# I2C_Jog_Controller.net
KiCad netlist of a schematic drawn in Altium Designer
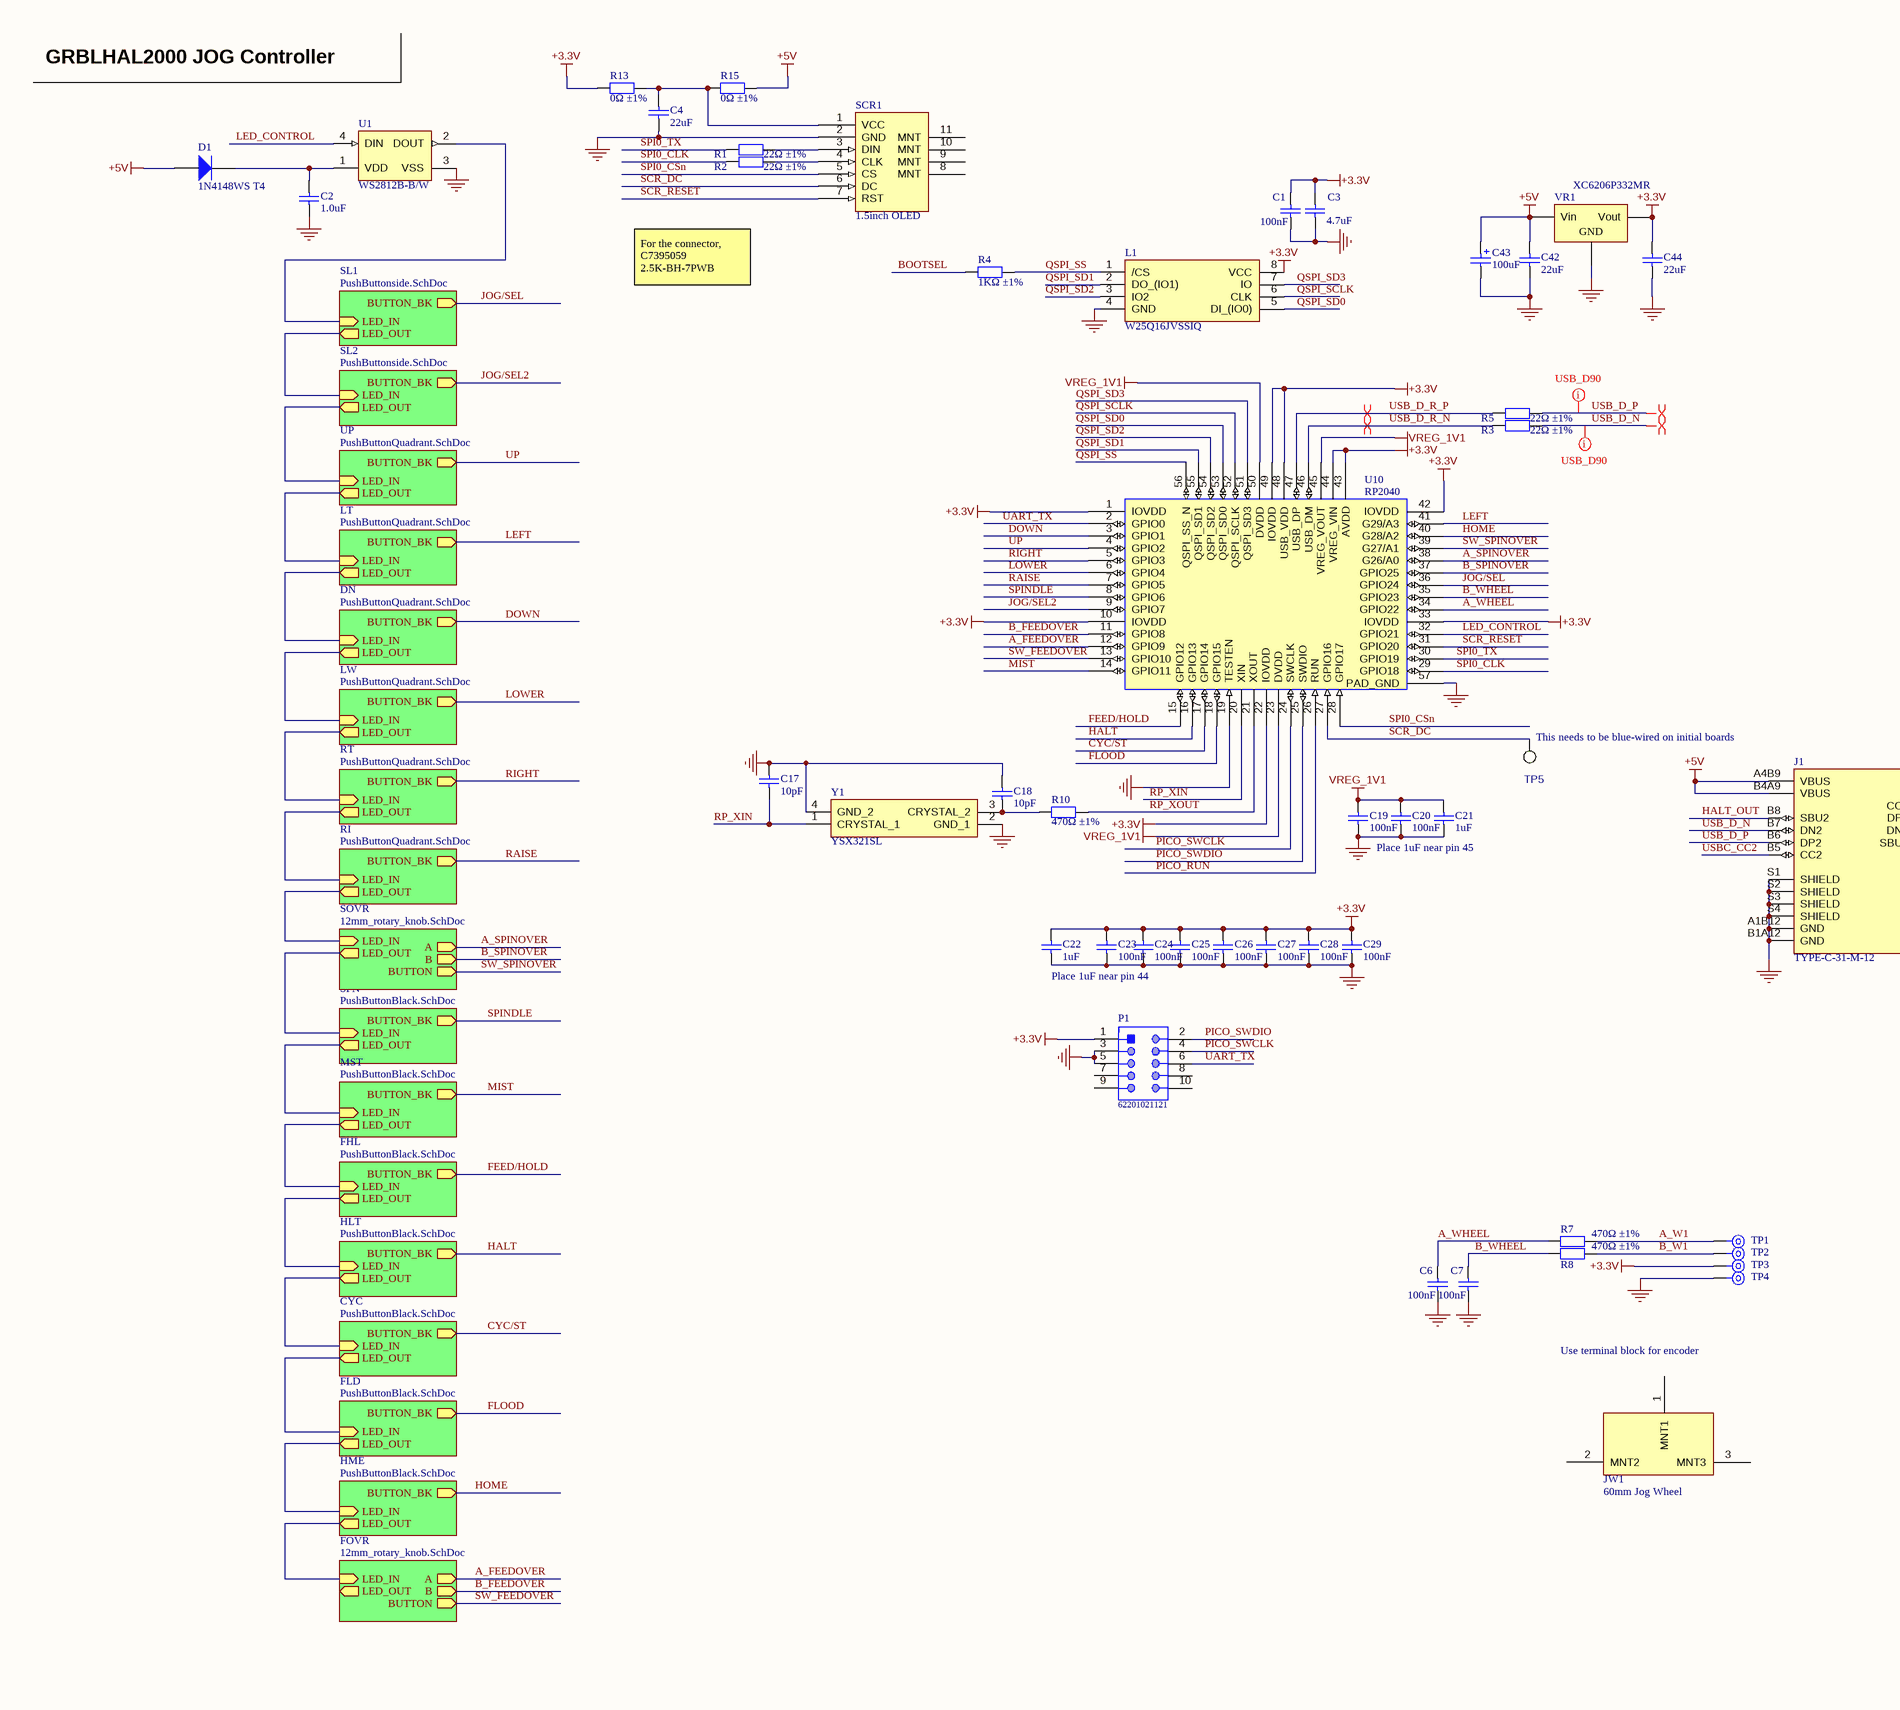
[diagram p0: I2C_Jog_Controller.SchDoc, left]
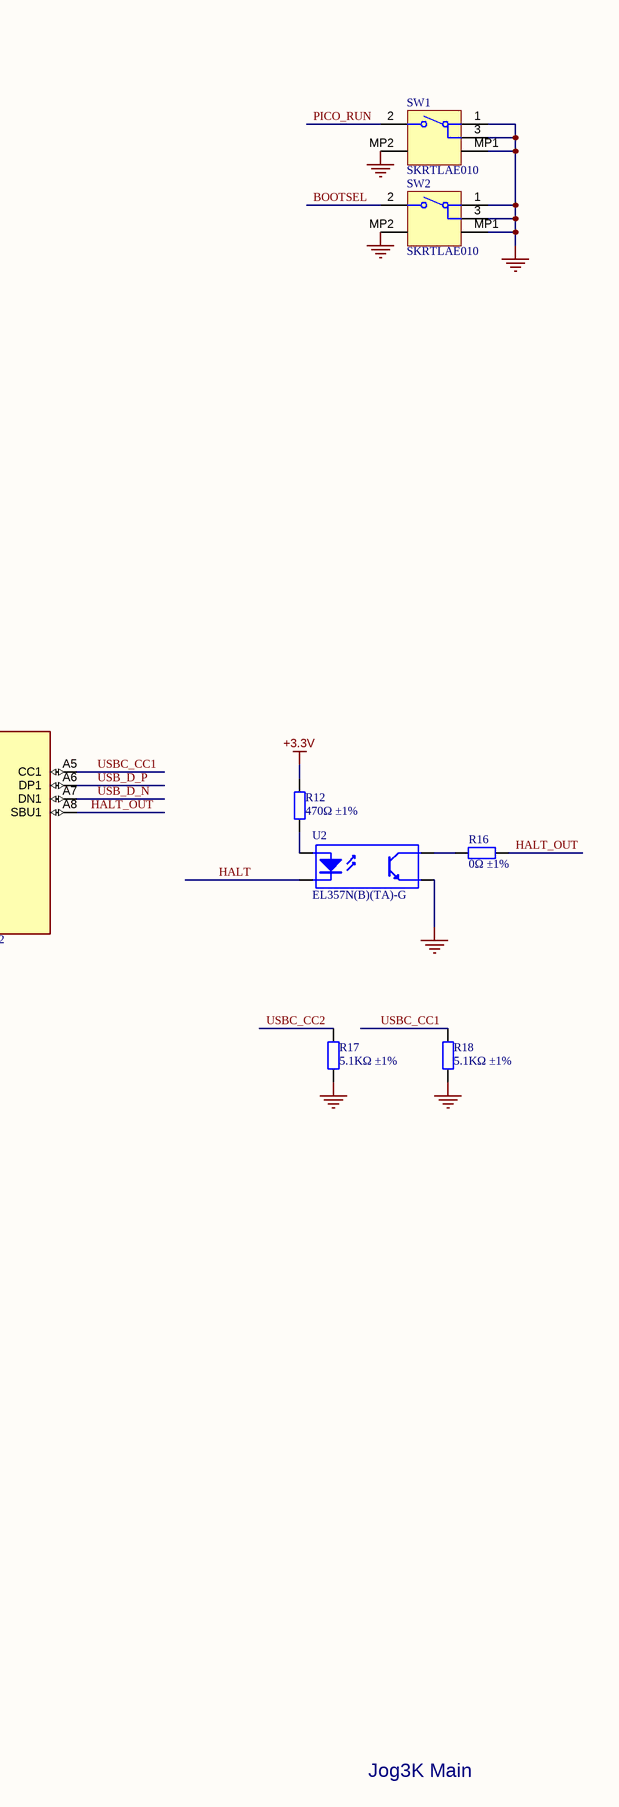
[diagram p1: I2C_Jog_Controller.SchDoc, right]

(export (version "E")
  (design (tool "Eeschema 10.0.6"))
  (components
    (comp (ref "C1")
      (value "100nF")
      (footprint "0603_C")
      (description "Chip capacitors")
      (fields (field (name "MANUFACTURER") "YAGEO") (field (name "PARTNUMBER") "CC0603KRX7R9BB104"))
      (libsource (lib "Cap") (part "0603 100nF (104) 10% 50V"))
    )
    (comp (ref "C2")
      (value "1.0uF")
      (footprint "0402_C")
      (description "Chip capacitor")
      (fields
        (field (name "MANUFACTURER") "Samsung Electro-Mechanics")
        (field (name "PARTNUMBER") "CL05A105KA5NQNC")
      )
      (libsource (lib "Cap") (part "0402 1.0uF (105) 10% 25V"))
    )
    (comp (ref "C3")
      (value "4.7uF")
      (footprint "0603_C")
      (description "Chip capacitors")
      (fields
        (field (name "MANUFACTURER") "Samsung Electro-Mechanics")
        (field (name "PARTNUMBER") "CL10A475KO8NNNC")
      )
      (libsource (lib "Cap") (part "0603 4.7uF (475) 10% 16V"))
    )
    (comp (ref "C4")
      (value "22uF")
      (footprint "0805_C")
      (description "Chip capacitors")
      (fields
        (field (name "MANUFACTURER") "Samsung Electro-Mechanics")
        (field (name "PARTNUMBER") "CL21A226MAQNNNE")
      )
      (libsource (lib "Cap") (part "0805 22uF (226) 20% 25V"))
    )
    (comp (ref "C6")
      (value "100nF")
      (footprint "0603_C")
      (description "Chip capacitors")
      (fields (field (name "MANUFACTURER") "YAGEO") (field (name "PARTNUMBER") "CC0603KRX7R9BB104"))
      (libsource (lib "Cap") (part "0603 100nF (104) 10% 50V"))
    )
    (comp (ref "C7")
      (value "100nF")
      (footprint "0603_C")
      (description "Chip capacitors")
      (fields (field (name "MANUFACTURER") "YAGEO") (field (name "PARTNUMBER") "CC0603KRX7R9BB104"))
      (libsource (lib "Cap") (part "0603 100nF (104) 10% 50V"))
    )
    (comp (ref "C17")
      (value "10pF")
      (footprint "0603_C")
      (description "Chip capacitors")
      (fields
        (field (name "MANUFACTURER") "Samsung Electro-Mechanics")
        (field (name "PARTNUMBER") "CL10C100JB8NNNC")
      )
      (libsource (lib "Cap") (part "0603 10pF (100) 5% 50V"))
    )
    (comp (ref "C18")
      (value "10pF")
      (footprint "0603_C")
      (description "Chip capacitors")
      (fields
        (field (name "MANUFACTURER") "Samsung Electro-Mechanics")
        (field (name "PARTNUMBER") "CL10C100JB8NNNC")
      )
      (libsource (lib "Cap") (part "0603 10pF (100) 5% 50V"))
    )
    (comp (ref "C19")
      (value "100nF")
      (footprint "0603_C")
      (description "Chip capacitors")
      (fields (field (name "MANUFACTURER") "YAGEO") (field (name "PARTNUMBER") "CC0603KRX7R9BB104"))
      (libsource (lib "Cap") (part "0603 100nF (104) 10% 50V"))
    )
    (comp (ref "C20")
      (value "100nF")
      (footprint "0603_C")
      (description "Chip capacitors")
      (fields (field (name "MANUFACTURER") "YAGEO") (field (name "PARTNUMBER") "CC0603KRX7R9BB104"))
      (libsource (lib "Cap") (part "0603 100nF (104) 10% 50V"))
    )
    (comp (ref "C21")
      (value "1uF")
      (footprint "0603_C")
      (description "Chip capacitors")
      (fields
        (field (name "MANUFACTURER") "Samsung Electro-Mechanics")
        (field (name "PARTNUMBER") "CL10A105KB8NNNC")
      )
      (libsource (lib "Cap") (part "0603 1uF (105) 10% 50V"))
    )
    (comp (ref "C22")
      (value "1uF")
      (footprint "0603_C")
      (description "Chip capacitors")
      (fields
        (field (name "MANUFACTURER") "Samsung Electro-Mechanics")
        (field (name "PARTNUMBER") "CL10A105KB8NNNC")
      )
      (libsource (lib "Cap") (part "0603 1uF (105) 10% 50V"))
    )
    (comp (ref "C23")
      (value "100nF")
      (footprint "0603_C")
      (description "Chip capacitors")
      (fields (field (name "MANUFACTURER") "YAGEO") (field (name "PARTNUMBER") "CC0603KRX7R9BB104"))
      (libsource (lib "Cap") (part "0603 100nF (104) 10% 50V"))
    )
    (comp (ref "C24")
      (value "100nF")
      (footprint "0603_C")
      (description "Chip capacitors")
      (fields (field (name "MANUFACTURER") "YAGEO") (field (name "PARTNUMBER") "CC0603KRX7R9BB104"))
      (libsource (lib "Cap") (part "0603 100nF (104) 10% 50V"))
    )
    (comp (ref "C25")
      (value "100nF")
      (footprint "0603_C")
      (description "Chip capacitors")
      (fields (field (name "MANUFACTURER") "YAGEO") (field (name "PARTNUMBER") "CC0603KRX7R9BB104"))
      (libsource (lib "Cap") (part "0603 100nF (104) 10% 50V"))
    )
    (comp (ref "C26")
      (value "100nF")
      (footprint "0603_C")
      (description "Chip capacitors")
      (fields (field (name "MANUFACTURER") "YAGEO") (field (name "PARTNUMBER") "CC0603KRX7R9BB104"))
      (libsource (lib "Cap") (part "0603 100nF (104) 10% 50V"))
    )
    (comp (ref "C27")
      (value "100nF")
      (footprint "0603_C")
      (description "Chip capacitors")
      (fields (field (name "MANUFACTURER") "YAGEO") (field (name "PARTNUMBER") "CC0603KRX7R9BB104"))
      (libsource (lib "Cap") (part "0603 100nF (104) 10% 50V"))
    )
    (comp (ref "C28")
      (value "100nF")
      (footprint "0603_C")
      (description "Chip capacitors")
      (fields (field (name "MANUFACTURER") "YAGEO") (field (name "PARTNUMBER") "CC0603KRX7R9BB104"))
      (libsource (lib "Cap") (part "0603 100nF (104) 10% 50V"))
    )
    (comp (ref "C29")
      (value "100nF")
      (footprint "0603_C")
      (description "Chip capacitors")
      (fields (field (name "MANUFACTURER") "YAGEO") (field (name "PARTNUMBER") "CC0603KRX7R9BB104"))
      (libsource (lib "Cap") (part "0603 100nF (104) 10% 50V"))
    )
    (comp (ref "C42")
      (value "22uF")
      (footprint "0805_C")
      (description "Chip capacitors")
      (fields
        (field (name "MANUFACTURER") "Samsung Electro-Mechanics")
        (field (name "PARTNUMBER") "CL21A226MAQNNNE")
      )
      (libsource (lib "Cap") (part "0805 22uF (226) 20% 25V"))
    )
    (comp (ref "C43")
      (value "100uF")
      (footprint "CASE-B_3528")
      (description "Tantalum capacitor")
      (fields (field (name "MANUFACTURER") "AVX") (field (name "PARTNUMBER") "TAJB107K006RNJ"))
      (libsource (lib "Cap") (part "3528 100uF (107) 10% 6.3V"))
    )
    (comp (ref "C44")
      (value "22uF")
      (footprint "0805_C")
      (description "Chip capacitors")
      (fields
        (field (name "MANUFACTURER") "Samsung Electro-Mechanics")
        (field (name "PARTNUMBER") "CL21A226MAQNNNE")
      )
      (libsource (lib "Cap") (part "0805 22uF (226) 20% 25V"))
    )
    (comp (ref "D1")
      (value "1N4148WS T4")
      (footprint "SOD-323")
      (description "二极管")
      (libsource (lib "Diode") (part "SOD-323 1N4148WS T4"))
    )
    (comp (ref "J1")
      (value "TYPE-C-31-M-12")
      (footprint "HRO_TYPE-C-31-M-12")
      (description "USB Connectors 24 Receptacle 1 8.94*7.3mm RoHS")
      (fields (field (name "MF") "HRO Electronics Co., Ltd."))
      (libsource (lib "Universal_CNC_Breakout") (part "TYPE-C-31-M-12"))
    )
    (comp (ref "JW1")
      (value "60mm Jog Wheel")
      (footprint "60mm_Jog_wheel")
      (libsource (lib "I2C_Jog_Controller") (part "60mm_Jog_Wheel"))
    )
    (comp (ref "L1")
      (value "W25Q16JVSSIQ")
      (footprint "SamacSys:SOIC127P780X195-8N")
      (description "SPI NOR FLASH 16Mbit")
      (libsource (lib "*") (part "W25Q128JVSIQ_TR"))
    )
    (comp (ref "P1")
      (value "62201021121")
      (footprint "62201021121")
      (description "THT Vertical Pin Header WR-PHD, Pitch 1.27 mm, Dual Row, 10 pins")
      (fields (field (name "MANUFACTURER") "Wurth Elektronik") (field (name "PUBLISHER") "WurthElektronik"))
      (libsource (lib "Altium Content Vault") (part "WE-CN-2P-M-R10"))
    )
    (comp (ref "R1")
      (value "22Ω ±1%")
      (footprint "0603_R")
      (description "Chip resistor")
      (fields (field (name "MANUFACTURER") "Uniroyal Elec") (field (name "PARTNUMBER") "0603WAF220JT5E"))
      (libsource (lib "RES") (part "0603 22R (22R0) 1%"))
    )
    (comp (ref "R2")
      (value "22Ω ±1%")
      (footprint "0603_R")
      (description "Chip resistor")
      (fields (field (name "MANUFACTURER") "Uniroyal Elec") (field (name "PARTNUMBER") "0603WAF220JT5E"))
      (libsource (lib "RES") (part "0603 22R (22R0) 1%"))
    )
    (comp (ref "R3")
      (value "22Ω ±1%")
      (footprint "0603_R")
      (description "Chip resistor")
      (fields (field (name "MANUFACTURER") "Uniroyal Elec") (field (name "PARTNUMBER") "0603WAF220JT5E"))
      (libsource (lib "RES") (part "0603 22R (22R0) 1%"))
    )
    (comp (ref "R4")
      (value "1KΩ ±1%")
      (footprint "0603_R")
      (description "Chip resistor")
      (fields (field (name "MANUFACTURER") "Uniroyal Elec") (field (name "PARTNUMBER") "0603WAF1001T5E"))
      (libsource (lib "RES") (part "0603 1K (1001) 1%"))
    )
    (comp (ref "R5")
      (value "22Ω ±1%")
      (footprint "0603_R")
      (description "Chip resistor")
      (fields (field (name "MANUFACTURER") "Uniroyal Elec") (field (name "PARTNUMBER") "0603WAF220JT5E"))
      (libsource (lib "RES") (part "0603 22R (22R0) 1%"))
    )
    (comp (ref "R7")
      (value "470Ω ±1%")
      (footprint "0603_R")
      (description "Chip resistor")
      (fields (field (name "MANUFACTURER") "Uniroyal Elec") (field (name "PARTNUMBER") "0603WAF4700T5E"))
      (libsource (lib "RES") (part "0603 470R (4700) 1%"))
    )
    (comp (ref "R8")
      (value "470Ω ±1%")
      (footprint "0603_R")
      (description "Chip resistor")
      (fields (field (name "MANUFACTURER") "Uniroyal Elec") (field (name "PARTNUMBER") "0603WAF4700T5E"))
      (libsource (lib "RES") (part "0603 470R (4700) 1%"))
    )
    (comp (ref "R10")
      (value "470Ω ±1%")
      (footprint "0603_R")
      (description "Chip resistor")
      (fields (field (name "MANUFACTURER") "Uniroyal Elec") (field (name "PARTNUMBER") "0603WAF4700T5E"))
      (libsource (lib "RES") (part "0603 470R (4700) 1%"))
    )
    (comp (ref "R12")
      (value "470Ω ±1%")
      (footprint "0603_R")
      (description "Chip resistor")
      (fields (field (name "MANUFACTURER") "Uniroyal Elec") (field (name "PARTNUMBER") "0603WAF4700T5E"))
      (libsource (lib "") (part "0603 470R (4700) 1%_1"))
    )
    (comp (ref "R13")
      (value "0Ω ±1%")
      (footprint "0603_R")
      (description "Chip resistor")
      (fields (field (name "MANUFACTURER") "Uniroyal Elec") (field (name "PARTNUMBER") "0603WAF0000T5E"))
      (libsource (lib "RES") (part "0603 0R (0R0) 1%"))
    )
    (comp (ref "R15")
      (value "0Ω ±1%")
      (footprint "0603_R")
      (description "Chip resistor")
      (fields (field (name "MANUFACTURER") "Uniroyal Elec") (field (name "PARTNUMBER") "0603WAF0000T5E"))
      (libsource (lib "RES") (part "0603 0R (0R0) 1%"))
    )
    (comp (ref "R16")
      (value "0Ω ±1%")
      (footprint "0603_R")
      (description "Chip resistor")
      (fields (field (name "MANUFACTURER") "Uniroyal Elec") (field (name "PARTNUMBER") "0603WAF0000T5E"))
      (libsource (lib "RES") (part "0603 0R (0R0) 1%"))
    )
    (comp (ref "R17")
      (value "5.1KΩ ±1%")
      (footprint "0603_R")
      (description "Chip resistor")
      (fields (field (name "MANUFACTURER") "Uniroyal Elec") (field (name "PARTNUMBER") "0603WAF5101T5E"))
      (libsource (lib "RES") (part "0603 5.1K (5101) 1%"))
    )
    (comp (ref "R18")
      (value "5.1KΩ ±1%")
      (footprint "0603_R")
      (description "Chip resistor")
      (fields (field (name "MANUFACTURER") "Uniroyal Elec") (field (name "PARTNUMBER") "0603WAF5101T5E"))
      (libsource (lib "RES") (part "0603 5.1K (5101) 1%"))
    )
    (comp (ref "SCR1")
      (value "1.5inch OLED")
      (footprint "1.5inch_Waveshare_OLED")
      (libsource (lib "I2C_Jog_Controller") (part "1.5inch Waveshare OLED screen"))
    )
    (comp (ref "SW1")
      (value "SKRTLAE010")
      (footprint "ALPS-SKRTLAE010_V")
      (description "Side Push Type, 250 V, -40 to 90 degC, 3-Pin SMD, RoHS, Tape and Reel")
      (fields (field (name "MANUFACTURER") "ALPS"))
      (libsource (lib "Altium Content Vault") (part "SW_SPST-3_A"))
    )
    (comp (ref "SW2")
      (value "SKRTLAE010")
      (footprint "ALPS-SKRTLAE010_V")
      (description "Side Push Type, 250 V, -40 to 90 degC, 3-Pin SMD, RoHS, Tape and Reel")
      (fields (field (name "MANUFACTURER") "ALPS"))
      (libsource (lib "Altium Content Vault") (part "SW_SPST-3_A"))
    )
    (comp (ref "TP1")
      (value "2.5mm TP")
      (footprint "TP_SQ_2.5mm")
      (description "2.5mm x 3.5mm pad")
      (libsource (lib "Universal_CNC_Breakout") (part "TL_5017"))
    )
    (comp (ref "TP2")
      (value "2.5mm TP")
      (footprint "TP_SQ_2.5mm")
      (description "2.5mm x 3.5mm pad")
      (libsource (lib "Universal_CNC_Breakout") (part "TL_5017"))
    )
    (comp (ref "TP3")
      (value "2.5mm TP")
      (footprint "TP_SQ_2.5mm")
      (description "2.5mm x 3.5mm pad")
      (libsource (lib "Universal_CNC_Breakout") (part "TL_5017"))
    )
    (comp (ref "TP4")
      (value "2.5mm TP")
      (footprint "TP_SQ_2.5mm")
      (description "2.5mm x 3.5mm pad")
      (libsource (lib "Universal_CNC_Breakout") (part "TL_5017"))
    )
    (comp (ref "TP5")
      (value "TESTPOINT")
      (footprint "TP/SMALL")
      (description "Test Point")
      (libsource (lib "Sienci_Labs") (part "TESTPOINT"))
    )
    (comp (ref "U1")
      (value "WS2812B-B/W")
      (footprint "ADA-RGB-1655_V")
      (fields (field (name "MANUFACTURER") "Worldsemi"))
      (libsource (lib "Altium Content Vault") (part "ADA-RGB-1655-4"))
    )
    (comp (ref "U2")
      (value "EL357N(B)(TA)-G")
      (footprint "Miscellaneous Devices LC:SOP-4_P2.54")
      (description "OPTOISOLATOR 3.75KV TRANS 4-SOP")
      (libsource (lib "IC") (part "EL357N(B)(TA)-G_[C6649]"))
    )
    (comp (ref "U10")
      (value "RP2040")
      (footprint "RP2040")
      (description "RP2040 First MCU from RPI")
      (libsource (lib "Universal_CNC_Breakout") (part "RP2040"))
    )
    (comp (ref "VR1")
      (value "XC6206P332MR")
      (footprint "SOT-23-3L")
      (description "200mA 680mV@(100mA) Fixed 3.3V~3.3V Positive 1 6V SOT-23-3L Linear Voltage Regulators (LDO) ROHS")
      (libsource (lib "LDO") (part "SOT-23 XC6206P332MR"))
    )
    (comp (ref "Y1")
      (value "YSX321SL")
      (footprint "SamacSys:YSX321SL")
      (description "Crystal or Oscillator")
      (libsource (lib "*") (part "YSX321SL"))
    )
  )
  (nets
    (net (code "1") (name "+3.3V") (class "Default")
      (node (ref "C1") (pin "2") (pinfunction "2_2") (pintype "passive"))
      (node (ref "C22") (pin "2") (pinfunction "2_2") (pintype "passive"))
      (node (ref "C23") (pin "2") (pinfunction "2_2") (pintype "passive"))
      (node (ref "C24") (pin "2") (pinfunction "2_2") (pintype "passive"))
      (node (ref "C25") (pin "2") (pinfunction "2_2") (pintype "passive"))
      (node (ref "C26") (pin "2") (pinfunction "2_2") (pintype "passive"))
      (node (ref "C27") (pin "2") (pinfunction "2_2") (pintype "passive"))
      (node (ref "C28") (pin "2") (pinfunction "2_2") (pintype "passive"))
      (node (ref "C29") (pin "2") (pinfunction "2_2") (pintype "passive"))
      (node (ref "C3") (pin "2") (pinfunction "2_2") (pintype "passive"))
      (node (ref "C44") (pin "2") (pinfunction "2_2") (pintype "passive"))
      (node (ref "L1") (pin "8") (pinfunction "VCC_8") (pintype "passive"))
      (node (ref "P1") (pin "1") (pinfunction "1_1") (pintype "passive"))
      (node (ref "R12") (pin "2") (pinfunction "2_2") (pintype "passive"))
      (node (ref "R13") (pin "2") (pinfunction "2_2") (pintype "passive"))
      (node (ref "TP3") (pin "1") (pinfunction "1_1") (pintype "passive"))
      (node (ref "U10") (pin "1") (pinfunction "IOVDD_1") (pintype "power_in"))
      (node (ref "U10") (pin "10") (pinfunction "IOVDD_10") (pintype "power_in"))
      (node (ref "U10") (pin "22") (pinfunction "IOVDD_22") (pintype "power_in"))
      (node (ref "U10") (pin "33") (pinfunction "IOVDD_33") (pintype "power_in"))
      (node (ref "U10") (pin "42") (pinfunction "IOVDD_42") (pintype "power_in"))
      (node (ref "U10") (pin "43") (pinfunction "AVDD_43") (pintype "power_in"))
      (node (ref "U10") (pin "44") (pinfunction "VREG_VIN_44") (pintype "power_in"))
      (node (ref "U10") (pin "48") (pinfunction "USB_VDD_48") (pintype "power_in"))
      (node (ref "U10") (pin "49") (pinfunction "IOVDD_49") (pintype "power_in"))
      (node (ref "VR1") (pin "2") (pinfunction "Vout_2") (pintype "passive"))
    )
    (net (code "2") (name "+5V") (class "Default")
      (node (ref "C42") (pin "2") (pinfunction "2_2") (pintype "passive"))
      (node (ref "C43") (pin "1") (pinfunction "1_1") (pintype "passive"))
      (node (ref "D1") (pin "1") (pinfunction "A_1") (pintype "passive"))
      (node (ref "J1") (pin "A4B9") (pinfunction "VBUS_A4B9") (pintype "power_in"))
      (node (ref "J1") (pin "B4A9") (pinfunction "VBUS_B4A9") (pintype "power_in"))
      (node (ref "R15") (pin "1") (pinfunction "1_1") (pintype "passive"))
      (node (ref "VR1") (pin "3") (pinfunction "Vin_3") (pintype "passive"))
    )
    (net (code "3") (name "/A_FEEDOVER") (class "Default")
      (node (ref "U10") (pin "12") (pinfunction "GPIO9_12") (pintype "bidirectional"))
    )
    (net (code "4") (name "/A_SPINOVER") (class "Default")
      (node (ref "U10") (pin "38") (pinfunction "G26/A0_38") (pintype "bidirectional"))
    )
    (net (code "5") (name "/A_W1") (class "Default")
      (node (ref "R7") (pin "2") (pinfunction "2_2") (pintype "passive"))
      (node (ref "TP1") (pin "1") (pinfunction "1_1") (pintype "passive"))
    )
    (net (code "6") (name "/A_WHEEL") (class "Default")
      (node (ref "C6") (pin "2") (pinfunction "2_2") (pintype "passive"))
      (node (ref "R7") (pin "1") (pinfunction "1_1") (pintype "passive"))
      (node (ref "U10") (pin "34") (pinfunction "GPIO22_34") (pintype "bidirectional"))
    )
    (net (code "7") (name "/BOOTSEL") (class "Default")
      (node (ref "R4") (pin "1") (pinfunction "1_1") (pintype "passive"))
      (node (ref "SW2") (pin "2") (pinfunction "2_2") (pintype "passive"))
    )
    (net (code "8") (name "/B_FEEDOVER") (class "Default")
      (node (ref "U10") (pin "11") (pinfunction "GPIO8_11") (pintype "bidirectional"))
    )
    (net (code "9") (name "/B_SPINOVER") (class "Default")
      (node (ref "U10") (pin "37") (pinfunction "GPIO25_37") (pintype "bidirectional"))
    )
    (net (code "10") (name "/B_W1") (class "Default")
      (node (ref "R8") (pin "2") (pinfunction "2_2") (pintype "passive"))
      (node (ref "TP2") (pin "1") (pinfunction "1_1") (pintype "passive"))
    )
    (net (code "11") (name "/B_WHEEL") (class "Default")
      (node (ref "C7") (pin "2") (pinfunction "2_2") (pintype "passive"))
      (node (ref "R8") (pin "1") (pinfunction "1_1") (pintype "passive"))
      (node (ref "U10") (pin "35") (pinfunction "GPIO23_35") (pintype "bidirectional"))
    )
    (net (code "12") (name "/CYC{slash}ST") (class "Default")
      (node (ref "U10") (pin "17") (pinfunction "GPIO14_17") (pintype "bidirectional"))
    )
    (net (code "13") (name "/DOWN") (class "Default")
      (node (ref "U10") (pin "3") (pinfunction "GPIO1_3") (pintype "bidirectional"))
    )
    (net (code "14") (name "/FEED{slash}HOLD") (class "Default")
      (node (ref "U10") (pin "15") (pinfunction "GPIO12_15") (pintype "bidirectional"))
    )
    (net (code "15") (name "/FLOOD") (class "Default")
      (node (ref "U10") (pin "18") (pinfunction "GPIO15_18") (pintype "bidirectional"))
    )
    (net (code "16") (name "/HALT") (class "Default")
      (node (ref "U10") (pin "16") (pinfunction "GPIO13_16") (pintype "bidirectional"))
      (node (ref "U2") (pin "2") (pinfunction "K_2") (pintype "passive"))
    )
    (net (code "17") (name "/HALT_OUT") (class "Default")
      (node (ref "J1") (pin "A8") (pinfunction "SBU1_A8") (pintype "bidirectional"))
      (node (ref "J1") (pin "B8") (pinfunction "SBU2_B8") (pintype "bidirectional"))
      (node (ref "R16") (pin "1") (pinfunction "1_1") (pintype "passive"))
    )
    (net (code "18") (name "/HOME") (class "Default")
      (node (ref "U10") (pin "40") (pinfunction "G28/A2_40") (pintype "bidirectional"))
    )
    (net (code "19") (name "/JOG{slash}SEL") (class "Default")
      (node (ref "U10") (pin "36") (pinfunction "GPIO24_36") (pintype "bidirectional"))
    )
    (net (code "20") (name "/JOG{slash}SEL2") (class "Default")
      (node (ref "U10") (pin "9") (pinfunction "GPIO7_9") (pintype "bidirectional"))
    )
    (net (code "21") (name "/LED_CONTROL") (class "Default")
      (node (ref "U1") (pin "4") (pinfunction "DIN_4") (pintype "input"))
      (node (ref "U10") (pin "32") (pinfunction "GPIO21_32") (pintype "bidirectional"))
    )
    (net (code "22") (name "/LED_IN") (class "Default")
      (node (ref "U1") (pin "2") (pinfunction "DOUT_2") (pintype "output"))
    )
    (net (code "40") (name "/LEFT") (class "Default")
      (node (ref "U10") (pin "41") (pinfunction "G29/A3_41") (pintype "bidirectional"))
    )
    (net (code "41") (name "/LOWER") (class "Default")
      (node (ref "U10") (pin "6") (pinfunction "GPIO4_6") (pintype "bidirectional"))
    )
    (net (code "42") (name "/MIST") (class "Default")
      (node (ref "U10") (pin "14") (pinfunction "GPIO11_14") (pintype "bidirectional"))
    )
    (net (code "43") (name "/PICO_RUN") (class "Default")
      (node (ref "SW1") (pin "2") (pinfunction "2_2") (pintype "passive"))
      (node (ref "U10") (pin "26") (pinfunction "RUN_26") (pintype "input"))
    )
    (net (code "44") (name "/PICO_SWCLK") (class "Default")
      (node (ref "P1") (pin "4") (pinfunction "4_4") (pintype "passive"))
      (node (ref "U10") (pin "24") (pinfunction "SWCLK_24") (pintype "bidirectional"))
    )
    (net (code "45") (name "/PICO_SWDIO") (class "Default")
      (node (ref "P1") (pin "2") (pinfunction "2_2") (pintype "passive"))
      (node (ref "U10") (pin "25") (pinfunction "SWDIO_25") (pintype "bidirectional"))
    )
    (net (code "46") (name "/QSPI_SCLK") (class "Default")
      (node (ref "L1") (pin "6") (pinfunction "CLK_6") (pintype "passive"))
      (node (ref "U10") (pin "52") (pinfunction "QSPI_SCLK_52") (pintype "bidirectional"))
    )
    (net (code "47") (name "/QSPI_SD0") (class "Default")
      (node (ref "L1") (pin "5") (pinfunction "DI_(IO0)_5") (pintype "passive"))
      (node (ref "U10") (pin "53") (pinfunction "QSPI_SD0_53") (pintype "bidirectional"))
    )
    (net (code "48") (name "/QSPI_SD1") (class "Default")
      (node (ref "L1") (pin "2") (pinfunction "DO_(IO1)_2") (pintype "passive"))
      (node (ref "U10") (pin "55") (pinfunction "QSPI_SD1_55") (pintype "bidirectional"))
    )
    (net (code "49") (name "/QSPI_SD2") (class "Default")
      (node (ref "L1") (pin "3") (pinfunction "IO2_3") (pintype "passive"))
      (node (ref "U10") (pin "54") (pinfunction "QSPI_SD2_54") (pintype "bidirectional"))
    )
    (net (code "50") (name "/QSPI_SD3") (class "Default")
      (node (ref "L1") (pin "7") (pinfunction "IO_7") (pintype "passive"))
      (node (ref "U10") (pin "51") (pinfunction "QSPI_SD3_51") (pintype "bidirectional"))
    )
    (net (code "51") (name "/QSPI_SS") (class "Default")
      (node (ref "L1") (pin "1") (pinfunction "/CS_1") (pintype "passive"))
      (node (ref "R4") (pin "2") (pinfunction "2_2") (pintype "passive"))
      (node (ref "U10") (pin "56") (pinfunction "QSPI_SS_N_56") (pintype "bidirectional"))
    )
    (net (code "52") (name "/RAISE") (class "Default")
      (node (ref "U10") (pin "7") (pinfunction "GPIO5_7") (pintype "bidirectional"))
    )
    (net (code "53") (name "/RIGHT") (class "Default")
      (node (ref "U10") (pin "5") (pinfunction "GPIO3_5") (pintype "bidirectional"))
    )
    (net (code "54") (name "/RP_XIN") (class "Default")
      (node (ref "C17") (pin "1") (pinfunction "1_1") (pintype "passive"))
      (node (ref "U10") (pin "20") (pinfunction "XIN_20") (pintype "passive"))
      (node (ref "Y1") (pin "1") (pinfunction "CRYSTAL_1_1") (pintype "passive"))
    )
    (net (code "55") (name "/RP_XOUT") (class "Default")
      (node (ref "R10") (pin "2") (pinfunction "2_2") (pintype "passive"))
      (node (ref "U10") (pin "21") (pinfunction "XOUT_21") (pintype "passive"))
    )
    (net (code "56") (name "/SCR_DC") (class "Default")
      (node (ref "SCR1") (pin "6") (pinfunction "DC_6") (pintype "input"))
      (node (ref "TP5") (pin "1") (pintype "passive"))
      (node (ref "U10") (pin "27") (pinfunction "GPIO16_27") (pintype "input"))
    )
    (net (code "57") (name "/SCR_RESET") (class "Default")
      (node (ref "SCR1") (pin "7") (pinfunction "RST_7") (pintype "input"))
      (node (ref "U10") (pin "31") (pinfunction "GPIO20_31") (pintype "bidirectional"))
    )
    (net (code "58") (name "/SPI0_CLK") (class "Default")
      (node (ref "R2") (pin "2") (pinfunction "2_2") (pintype "passive"))
      (node (ref "U10") (pin "29") (pinfunction "GPIO18_29") (pintype "bidirectional"))
    )
    (net (code "59") (name "/SPI0_CSn") (class "Default")
      (node (ref "SCR1") (pin "5") (pinfunction "CS_5") (pintype "input"))
      (node (ref "U10") (pin "28") (pinfunction "GPIO17_28") (pintype "input"))
    )
    (net (code "60") (name "/SPI0_TX") (class "Default")
      (node (ref "R1") (pin "2") (pinfunction "2_2") (pintype "passive"))
      (node (ref "U10") (pin "30") (pinfunction "GPIO19_30") (pintype "bidirectional"))
    )
    (net (code "61") (name "/SPINDLE") (class "Default")
      (node (ref "U10") (pin "8") (pinfunction "GPIO6_8") (pintype "bidirectional"))
    )
    (net (code "62") (name "/SW_FEEDOVER") (class "Default")
      (node (ref "U10") (pin "13") (pinfunction "GPIO10_13") (pintype "bidirectional"))
    )
    (net (code "63") (name "/SW_SPINOVER") (class "Default")
      (node (ref "U10") (pin "39") (pinfunction "G27/A1_39") (pintype "bidirectional"))
    )
    (net (code "64") (name "/UART_TX") (class "Default")
      (node (ref "P1") (pin "6") (pinfunction "6_6") (pintype "passive"))
      (node (ref "U10") (pin "2") (pinfunction "GPIO0_2") (pintype "bidirectional"))
    )
    (net (code "65") (name "/UP") (class "Default")
      (node (ref "U10") (pin "4") (pinfunction "GPIO2_4") (pintype "bidirectional"))
    )
    (net (code "66") (name "/USBC_CC1") (class "Default")
      (node (ref "J1") (pin "A5") (pinfunction "CC1_A5") (pintype "bidirectional"))
      (node (ref "R18") (pin "1") (pinfunction "1_1") (pintype "passive"))
    )
    (net (code "67") (name "/USBC_CC2") (class "Default")
      (node (ref "J1") (pin "B5") (pinfunction "CC2_B5") (pintype "bidirectional"))
      (node (ref "R17") (pin "1") (pinfunction "1_1") (pintype "passive"))
    )
    (net (code "68") (name "/USB_D_N") (class "Default")
      (node (ref "J1") (pin "A7") (pinfunction "DN1_A7") (pintype "bidirectional"))
      (node (ref "J1") (pin "B7") (pinfunction "DN2_B7") (pintype "bidirectional"))
      (node (ref "R3") (pin "1") (pinfunction "1_1") (pintype "passive"))
    )
    (net (code "69") (name "/USB_D_P") (class "Default")
      (node (ref "J1") (pin "A6") (pinfunction "DP1_A6") (pintype "bidirectional"))
      (node (ref "J1") (pin "B6") (pinfunction "DP2_B6") (pintype "bidirectional"))
      (node (ref "R5") (pin "1") (pinfunction "1_1") (pintype "passive"))
    )
    (net (code "70") (name "/USB_D_R_N") (class "Default")
      (node (ref "R3") (pin "2") (pinfunction "2_2") (pintype "passive"))
      (node (ref "U10") (pin "46") (pinfunction "USB_DM_46") (pintype "bidirectional"))
    )
    (net (code "71") (name "/USB_D_R_P") (class "Default")
      (node (ref "R5") (pin "2") (pinfunction "2_2") (pintype "passive"))
      (node (ref "U10") (pin "47") (pinfunction "USB_DP_47") (pintype "bidirectional"))
    )
    (net (code "72") (name "GND") (class "Default")
      (node (ref "C1") (pin "1") (pinfunction "1_1") (pintype "passive"))
      (node (ref "C17") (pin "2") (pinfunction "2_2") (pintype "passive"))
      (node (ref "C18") (pin "2") (pinfunction "2_2") (pintype "passive"))
      (node (ref "C19") (pin "1") (pinfunction "1_1") (pintype "passive"))
      (node (ref "C2") (pin "1") (pinfunction "1_1") (pintype "passive"))
      (node (ref "C20") (pin "1") (pinfunction "1_1") (pintype "passive"))
      (node (ref "C21") (pin "1") (pinfunction "1_1") (pintype "passive"))
      (node (ref "C22") (pin "1") (pinfunction "1_1") (pintype "passive"))
      (node (ref "C23") (pin "1") (pinfunction "1_1") (pintype "passive"))
      (node (ref "C24") (pin "1") (pinfunction "1_1") (pintype "passive"))
      (node (ref "C25") (pin "1") (pinfunction "1_1") (pintype "passive"))
      (node (ref "C26") (pin "1") (pinfunction "1_1") (pintype "passive"))
      (node (ref "C27") (pin "1") (pinfunction "1_1") (pintype "passive"))
      (node (ref "C28") (pin "1") (pinfunction "1_1") (pintype "passive"))
      (node (ref "C29") (pin "1") (pinfunction "1_1") (pintype "passive"))
      (node (ref "C3") (pin "1") (pinfunction "1_1") (pintype "passive"))
      (node (ref "C4") (pin "1") (pinfunction "1_1") (pintype "passive"))
      (node (ref "C42") (pin "1") (pinfunction "1_1") (pintype "passive"))
      (node (ref "C43") (pin "2") (pinfunction "2_2") (pintype "passive"))
      (node (ref "C44") (pin "1") (pinfunction "1_1") (pintype "passive"))
      (node (ref "C6") (pin "1") (pinfunction "1_1") (pintype "passive"))
      (node (ref "C7") (pin "1") (pinfunction "1_1") (pintype "passive"))
      (node (ref "J1") (pin "A1B12") (pinfunction "GND_A1B12") (pintype "power_in"))
      (node (ref "J1") (pin "B1A12") (pinfunction "GND_B1A12") (pintype "power_in"))
      (node (ref "J1") (pin "S1") (pinfunction "SHIELD_S1") (pintype "passive"))
      (node (ref "J1") (pin "S2") (pinfunction "SHIELD_S2") (pintype "passive"))
      (node (ref "J1") (pin "S3") (pinfunction "SHIELD_S3") (pintype "passive"))
      (node (ref "J1") (pin "S4") (pinfunction "SHIELD_S4") (pintype "passive"))
      (node (ref "L1") (pin "4") (pinfunction "GND_4") (pintype "passive"))
      (node (ref "P1") (pin "3") (pinfunction "3_3") (pintype "passive"))
      (node (ref "P1") (pin "5") (pinfunction "5_5") (pintype "passive"))
      (node (ref "R17") (pin "2") (pinfunction "2_2") (pintype "passive"))
      (node (ref "R18") (pin "2") (pinfunction "2_2") (pintype "passive"))
      (node (ref "SCR1") (pin "2") (pinfunction "GND_2") (pintype "passive"))
      (node (ref "SW1") (pin "1") (pinfunction "1_1") (pintype "passive"))
      (node (ref "SW1") (pin "3") (pinfunction "3_3") (pintype "passive"))
      (node (ref "SW1") (pin "MP1") (pinfunction "MP1_MP1") (pintype "passive"))
      (node (ref "SW1") (pin "MP2") (pinfunction "MP2_MP2") (pintype "passive"))
      (node (ref "SW2") (pin "1") (pinfunction "1_1") (pintype "passive"))
      (node (ref "SW2") (pin "3") (pinfunction "3_3") (pintype "passive"))
      (node (ref "SW2") (pin "MP1") (pinfunction "MP1_MP1") (pintype "passive"))
      (node (ref "SW2") (pin "MP2") (pinfunction "MP2_MP2") (pintype "passive"))
      (node (ref "TP4") (pin "1") (pinfunction "1_1") (pintype "passive"))
      (node (ref "U1") (pin "3") (pinfunction "VSS_3") (pintype "power_in"))
      (node (ref "U10") (pin "19") (pinfunction "TESTEN_19") (pintype "input"))
      (node (ref "U10") (pin "57") (pinfunction "PAD_GND_57") (pintype "passive"))
      (node (ref "U2") (pin "3") (pinfunction "E_3") (pintype "passive"))
      (node (ref "VR1") (pin "1") (pinfunction "GND_1") (pintype "passive"))
      (node (ref "Y1") (pin "2") (pinfunction "GND_1_2") (pintype "passive"))
      (node (ref "Y1") (pin "4") (pinfunction "GND_2_4") (pintype "passive"))
    )
    (net (code "73") (name "Net-(D1-K)") (class "Default")
      (node (ref "C2") (pin "2") (pinfunction "2_2") (pintype "passive"))
      (node (ref "D1") (pin "2") (pinfunction "K_2") (pintype "passive"))
      (node (ref "U1") (pin "1") (pinfunction "VDD_1") (pintype "power_in"))
    )
    (net (code "74") (name "Net-(SCR1-CLK)") (class "Default")
      (node (ref "R2") (pin "1") (pinfunction "1_1") (pintype "passive"))
      (node (ref "SCR1") (pin "4") (pinfunction "CLK_4") (pintype "input"))
    )
    (net (code "75") (name "Net-(SCR1-DIN)") (class "Default")
      (node (ref "R1") (pin "1") (pinfunction "1_1") (pintype "passive"))
      (node (ref "SCR1") (pin "3") (pinfunction "DIN_3") (pintype "input"))
    )
    (net (code "76") (name "Net-(SCR1-VCC)") (class "Default")
      (node (ref "C4") (pin "2") (pinfunction "2_2") (pintype "passive"))
      (node (ref "R13") (pin "1") (pinfunction "1_1") (pintype "passive"))
      (node (ref "R15") (pin "2") (pinfunction "2_2") (pintype "passive"))
      (node (ref "SCR1") (pin "1") (pinfunction "VCC_1") (pintype "power_in"))
    )
    (net (code "77") (name "Net-(U2-A)") (class "Default")
      (node (ref "R12") (pin "1") (pinfunction "1_1") (pintype "passive"))
      (node (ref "U2") (pin "1") (pinfunction "A_1") (pintype "passive"))
    )
    (net (code "78") (name "Net-(U2-C)") (class "Default")
      (node (ref "R16") (pin "2") (pinfunction "2_2") (pintype "passive"))
      (node (ref "U2") (pin "4") (pinfunction "C_4") (pintype "passive"))
    )
    (net (code "79") (name "Net-(Y1-CRYSTAL_2)") (class "Default")
      (node (ref "C18") (pin "1") (pinfunction "1_1") (pintype "passive"))
      (node (ref "R10") (pin "1") (pinfunction "1_1") (pintype "passive"))
      (node (ref "Y1") (pin "3") (pinfunction "CRYSTAL_2_3") (pintype "passive"))
    )
    (net (code "80") (name "VREG_1V1") (class "Default")
      (node (ref "C19") (pin "2") (pinfunction "2_2") (pintype "passive"))
      (node (ref "C20") (pin "2") (pinfunction "2_2") (pintype "passive"))
      (node (ref "C21") (pin "2") (pinfunction "2_2") (pintype "passive"))
      (node (ref "U10") (pin "23") (pinfunction "DVDD_23") (pintype "power_in"))
      (node (ref "U10") (pin "45") (pinfunction "VREG_VOUT_45") (pintype "power_in"))
      (node (ref "U10") (pin "50") (pinfunction "DVDD_50") (pintype "power_in"))
    )
    (net (code "81") (name "unconnected-(JW1-MNT1-Pad1)") (class "Default")
      (node (ref "JW1") (pin "1") (pinfunction "MNT1_1") (pintype "passive"))
    )
    (net (code "82") (name "unconnected-(JW1-MNT2-Pad2)") (class "Default")
      (node (ref "JW1") (pin "2") (pinfunction "MNT2_2") (pintype "passive"))
    )
    (net (code "83") (name "unconnected-(JW1-MNT3-Pad3)") (class "Default")
      (node (ref "JW1") (pin "3") (pinfunction "MNT3_3") (pintype "passive"))
    )
    (net (code "84") (name "unconnected-(P1-Pad7)") (class "Default")
      (node (ref "P1") (pin "7") (pinfunction "7_7") (pintype "passive"))
    )
    (net (code "85") (name "unconnected-(P1-Pad8)") (class "Default")
      (node (ref "P1") (pin "8") (pinfunction "8_8") (pintype "passive"))
    )
    (net (code "86") (name "unconnected-(P1-Pad9)") (class "Default")
      (node (ref "P1") (pin "9") (pinfunction "9_9") (pintype "passive"))
    )
    (net (code "87") (name "unconnected-(P1-Pad10)") (class "Default")
      (node (ref "P1") (pin "10") (pinfunction "10_10") (pintype "passive"))
    )
    (net (code "88") (name "unconnected-(SCR1-MNT-Pad8)") (class "Default")
      (node (ref "SCR1") (pin "8") (pinfunction "MNT_8") (pintype "passive"))
    )
    (net (code "89") (name "unconnected-(SCR1-MNT-Pad9)") (class "Default")
      (node (ref "SCR1") (pin "9") (pinfunction "MNT_9") (pintype "passive"))
    )
    (net (code "90") (name "unconnected-(SCR1-MNT-Pad10)") (class "Default")
      (node (ref "SCR1") (pin "10") (pinfunction "MNT_10") (pintype "passive"))
    )
    (net (code "91") (name "unconnected-(SCR1-MNT-Pad11)") (class "Default")
      (node (ref "SCR1") (pin "11") (pinfunction "MNT_11") (pintype "passive"))
    )
  )
)
